# OpenEVSE_PLUS_v5_5.net
KiCad netlist of a schematic drawn in EAGLE
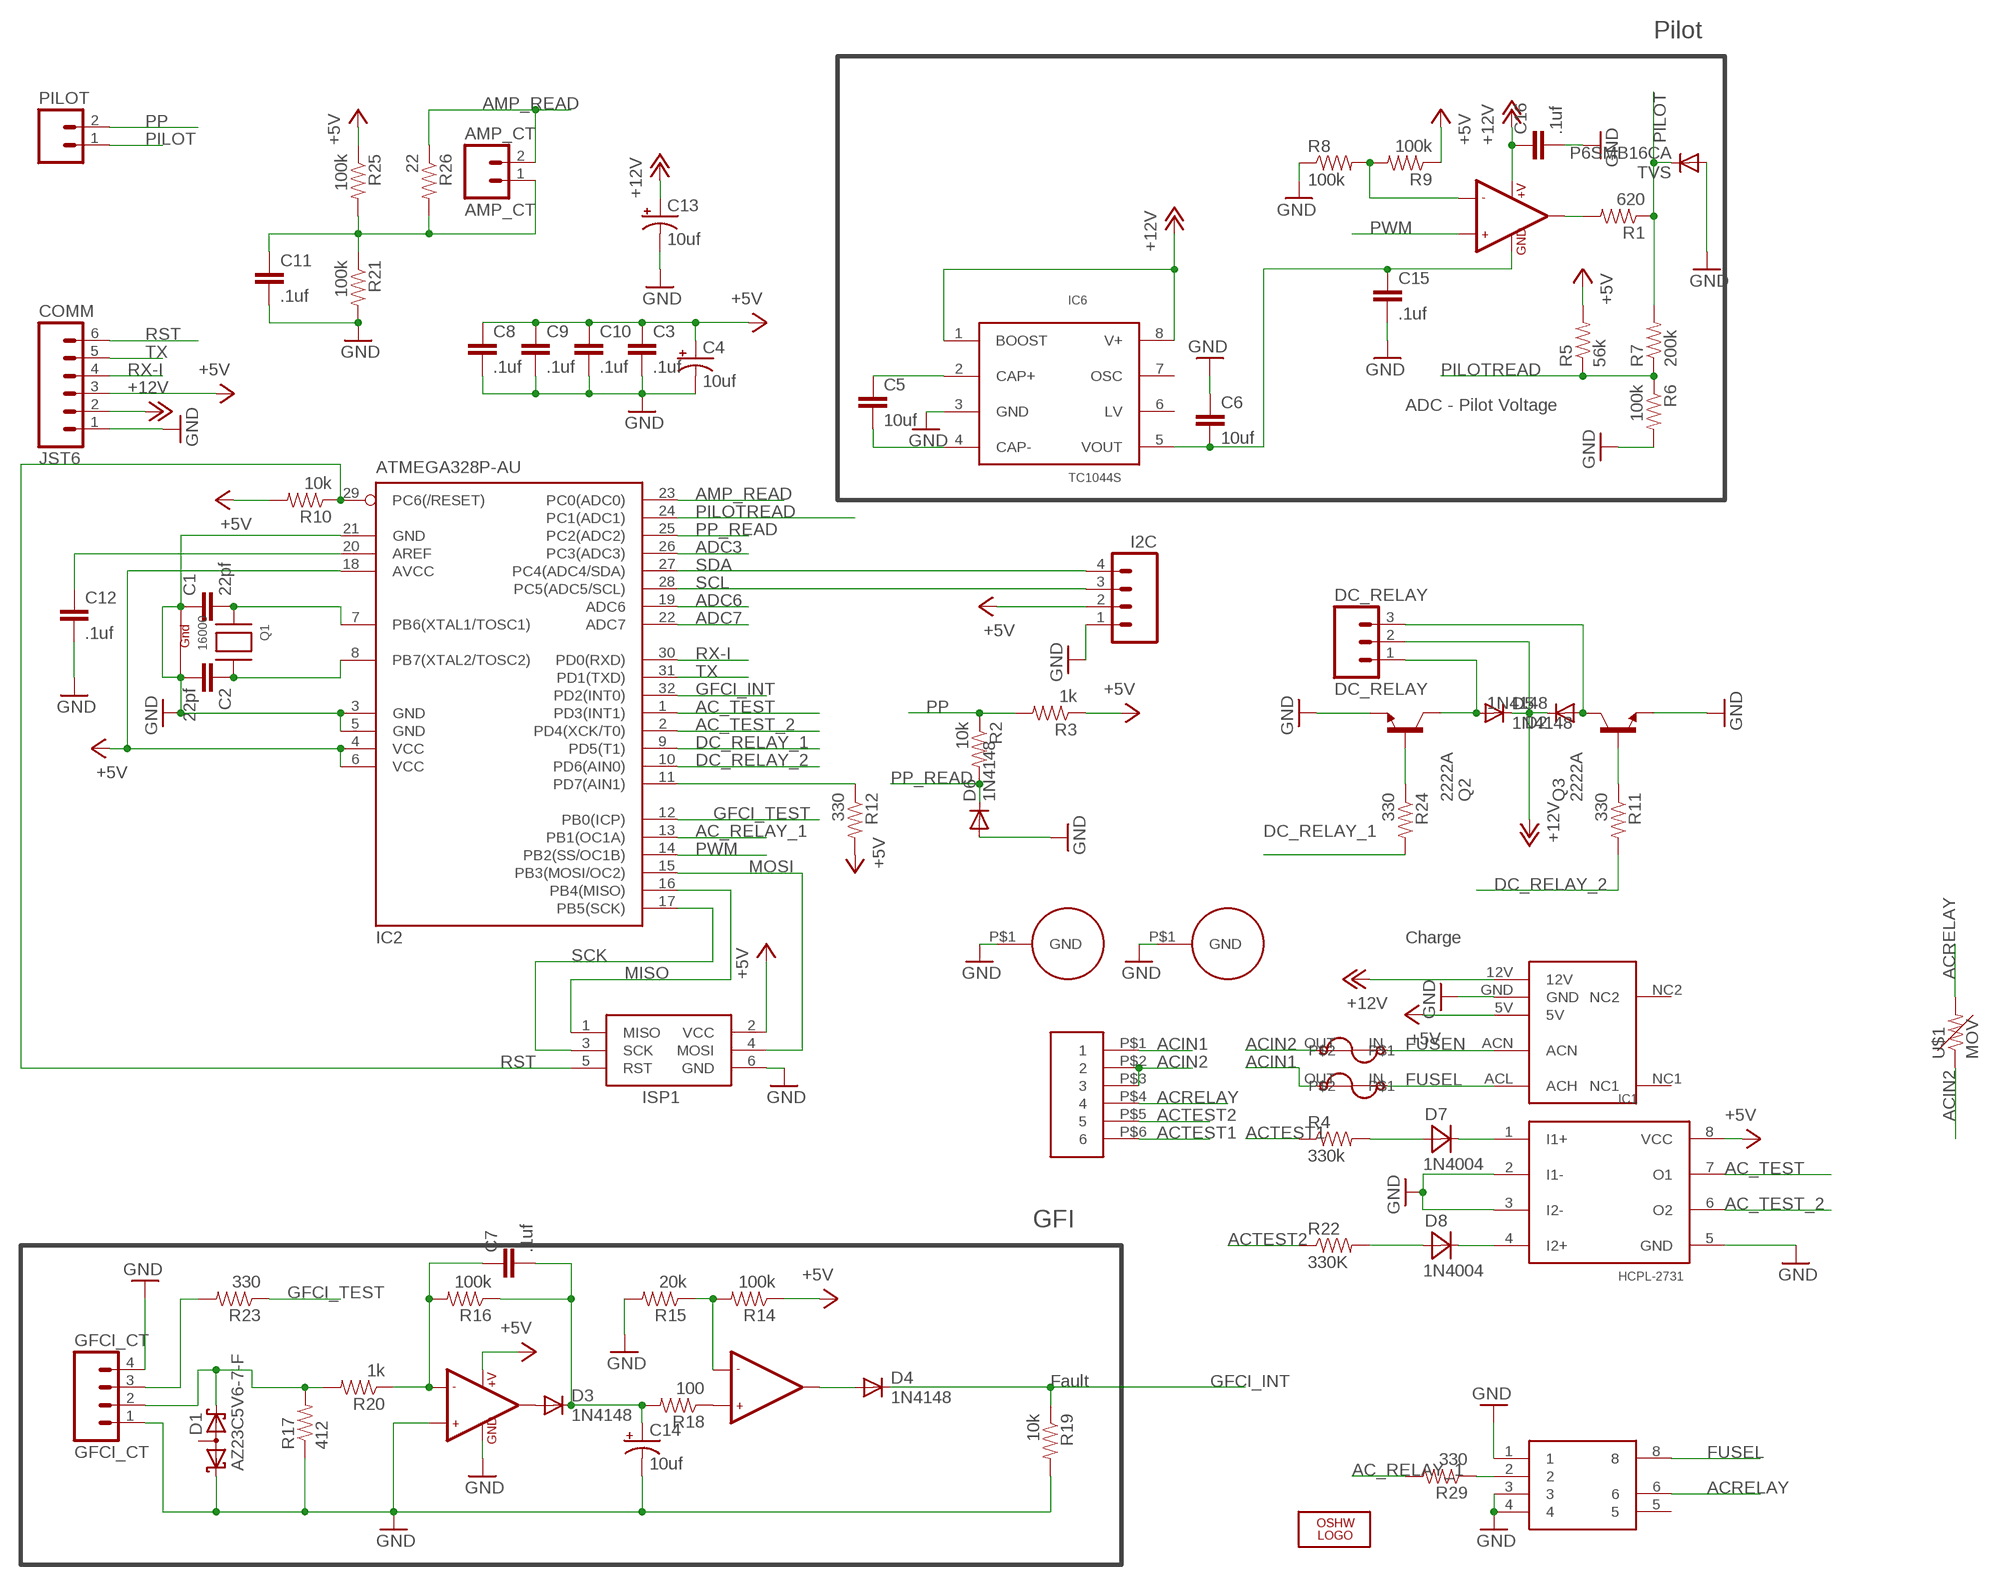
[diagram p0: schematic, sheet 1]

(export (version "E")
  (design (tool "Eeschema 10.0.6"))
  (components
    (comp (ref "AC")
      (value "JST-VH-6")
      (footprint "eagle-import:JST-VH-6")
      (libsource (lib "eagle-import") (part "JST-VH-6"))
    )
    (comp (ref "AMP_CT")
      (value "AMP_CT")
      (footprint "eagle-import:MOLEX_2")
      (libsource (lib "eagle-import") (part "MOLEX_2"))
    )
    (comp (ref "C1")
      (value "22pf")
      (footprint "eagle-import:0805")
      (libsource (lib "eagle-import") (part "CAP0805"))
    )
    (comp (ref "C2")
      (value "22pf")
      (footprint "eagle-import:0805")
      (libsource (lib "eagle-import") (part "CAP0805"))
    )
    (comp (ref "C3")
      (value ".1uf")
      (footprint "eagle-import:0805")
      (libsource (lib "eagle-import") (part "CAP0805"))
    )
    (comp (ref "C4")
      (value "10uf")
      (footprint "eagle-import:EIA3216")
      (libsource (lib "eagle-import") (part "CAP_POL1206"))
    )
    (comp (ref "C5")
      (value "10uf")
      (footprint "eagle-import:1206-CAP")
      (libsource (lib "eagle-import") (part "1.0UF50V10%(1206)"))
    )
    (comp (ref "C6")
      (value "10uf")
      (footprint "eagle-import:1206-CAP")
      (libsource (lib "eagle-import") (part "1.0UF50V10%(1206)"))
    )
    (comp (ref "C7")
      (value ".1uf")
      (footprint "eagle-import:0805")
      (libsource (lib "eagle-import") (part "CAP0805"))
    )
    (comp (ref "C8")
      (value ".1uf")
      (footprint "eagle-import:0805")
      (libsource (lib "eagle-import") (part "CAP0805"))
    )
    (comp (ref "C9")
      (value ".1uf")
      (footprint "eagle-import:0805")
      (libsource (lib "eagle-import") (part "CAP0805"))
    )
    (comp (ref "C10")
      (value ".1uf")
      (footprint "eagle-import:0805")
      (libsource (lib "eagle-import") (part "CAP0805"))
    )
    (comp (ref "C11")
      (value ".1uf")
      (footprint "eagle-import:0805")
      (libsource (lib "eagle-import") (part "CAP0805"))
    )
    (comp (ref "C12")
      (value ".1uf")
      (footprint "eagle-import:0805")
      (libsource (lib "eagle-import") (part "CAP0805"))
    )
    (comp (ref "C13")
      (value "10uf")
      (footprint "eagle-import:EIA3216")
      (libsource (lib "eagle-import") (part "CAP_POL1206"))
    )
    (comp (ref "C14")
      (value "10uf")
      (footprint "eagle-import:EIA3216")
      (libsource (lib "eagle-import") (part "CAP_POL1206"))
    )
    (comp (ref "C15")
      (value ".1uf")
      (footprint "eagle-import:0805")
      (libsource (lib "eagle-import") (part "CAP0805"))
    )
    (comp (ref "C16")
      (value ".1uf")
      (footprint "eagle-import:0805")
      (libsource (lib "eagle-import") (part "CAP0805"))
    )
    (comp (ref "COMM")
      (value "JST6")
      (footprint "eagle-import:JST6")
      (libsource (lib "eagle-import") (part "JST6"))
    )
    (comp (ref "D1")
      (value "AZ23C5V6-7-F")
      (footprint "eagle-import:SOT23")
      (libsource (lib "eagle-import") (part "BAS40-06"))
    )
    (comp (ref "D2")
      (value "1N4148")
      (footprint "eagle-import:SOD123")
      (libsource (lib "eagle-import") (part "DIODE-SOD123"))
    )
    (comp (ref "D3")
      (value "1N4148")
      (footprint "eagle-import:SOD123")
      (libsource (lib "eagle-import") (part "DIODE-SOD123"))
    )
    (comp (ref "D4")
      (value "1N4148")
      (footprint "eagle-import:SOD123")
      (libsource (lib "eagle-import") (part "DIODE-SOD123"))
    )
    (comp (ref "D5")
      (value "1N4148")
      (footprint "eagle-import:SOD123")
      (libsource (lib "eagle-import") (part "DIODE-SOD123"))
    )
    (comp (ref "D6")
      (value "1N4148")
      (footprint "eagle-import:SOD123")
      (libsource (lib "eagle-import") (part "DIODE-SOD123"))
    )
    (comp (ref "D7")
      (value "1N4004")
      (footprint "eagle-import:SMA")
      (libsource (lib "eagle-import") (part "MBRA340T3"))
    )
    (comp (ref "D8")
      (value "1N4004")
      (footprint "eagle-import:SMA")
      (libsource (lib "eagle-import") (part "MBRA340T3"))
    )
    (comp (ref "DC_RELAY")
      (value "DC_RELAY")
      (footprint "eagle-import:MOLEX_3")
      (libsource (lib "eagle-import") (part "MOLEX_3"))
    )
    (comp (ref "F1")
      (value "BEL1AFUSE")
      (footprint "eagle-import:BELFUSE1A")
      (libsource (lib "eagle-import") (part "BEL1AFUSE"))
    )
    (comp (ref "F2")
      (value "BEL1AFUSE")
      (footprint "eagle-import:BELFUSE1A")
      (libsource (lib "eagle-import") (part "BEL1AFUSE"))
    )
    (comp (ref "GFCI_CT")
      (value "GFCI_CT")
      (footprint "eagle-import:GFCI_4")
      (libsource (lib "eagle-import") (part "GFCI_4"))
    )
    (comp (ref "I2C")
      (value "M04JST-PTH-VERT")
      (footprint "eagle-import:JST-4-PTH-VERT")
      (libsource (lib "eagle-import") (part "M04JST-PTH-VERT"))
    )
    (comp (ref "IC1")
      (value "HCPL-2731")
      (footprint "eagle-import:DIP08")
      (libsource (lib "eagle-import") (part "HCPL-2731"))
    )
    (comp (ref "IC2")
      (value "ATMEGA328P-AU")
      (footprint "eagle-import:TQFP32-08")
      (fields (field (name "MPN") "ATMEGA8-16AU"))
      (libsource (lib "eagle-import") (part "MEGA8-AI"))
    )
    (comp (ref "IC3")
      (value "LM358")
      (footprint "eagle-import:SO08")
      (libsource (lib "eagle-import") (part "LMV358"))
    )
    (comp (ref "IC4")
      (value "LF353")
      (footprint "eagle-import:SO08")
      (libsource (lib "eagle-import") (part "LMV358"))
    )
    (comp (ref "IC5")
      (value "AQH1213")
      (footprint "eagle-import:DIP7")
      (libsource (lib "eagle-import") (part "AQH1213"))
    )
    (comp (ref "IC6")
      (value "TC1044S")
      (footprint "eagle-import:SO-8")
      (libsource (lib "eagle-import") (part "TC1044S"))
    )
    (comp (ref "ISP1")
      (value "AVRISP-6")
      (footprint "eagle-import:AVRISP")
      (libsource (lib "eagle-import") (part "AVRISP-6"))
    )
    (comp (ref "LOGO1")
      (value "OSHW_LOGO_8MILX0150-NT")
      (footprint "eagle-import:OSHW_8X150_NOTEXT")
      (libsource (lib "eagle-import") (part "OSHW_LOGO_8MILX0150-NT"))
    )
    (comp (ref "PILOT")
      (value "M025MM")
      (footprint "eagle-import:SCREWTERMINAL-5MM-2")
      (libsource (lib "eagle-import") (part "M025MM"))
    )
    (comp (ref "PS1")
      (value "MPM-04E-1205")
      (footprint "eagle-import:MPM-04E-1205")
      (libsource (lib "eagle-import") (part "MPM-04E-1205"))
    )
    (comp (ref "Q1")
      (value "16000")
      (footprint "eagle-import:NX3225")
      (libsource (lib "eagle-import") (part "XTAL-4-3225"))
    )
    (comp (ref "Q2")
      (value "2222A")
      (footprint "eagle-import:SOT23")
      (libsource (lib "eagle-import") (part "BCX70SMD"))
    )
    (comp (ref "Q3")
      (value "2222A")
      (footprint "eagle-import:SOT23")
      (libsource (lib "eagle-import") (part "BCX70SMD"))
    )
    (comp (ref "R1")
      (value "620")
      (footprint "eagle-import:0805")
      (libsource (lib "eagle-import") (part "RESISTOR0805-RES"))
    )
    (comp (ref "R2")
      (value "10k")
      (footprint "eagle-import:0805")
      (libsource (lib "eagle-import") (part "RESISTOR0805-RES"))
    )
    (comp (ref "R3")
      (value "1k")
      (footprint "eagle-import:0805")
      (libsource (lib "eagle-import") (part "RESISTOR0805-RES"))
    )
    (comp (ref "R4")
      (value "330k")
      (footprint "eagle-import:AXIAL-0.4")
      (libsource (lib "eagle-import") (part "RESISTORPTH-1/4W"))
    )
    (comp (ref "R5")
      (value "56k")
      (footprint "eagle-import:0805")
      (libsource (lib "eagle-import") (part "RESISTOR0805-RES"))
    )
    (comp (ref "R6")
      (value "100k")
      (footprint "eagle-import:0805")
      (libsource (lib "eagle-import") (part "RESISTOR0805-RES"))
    )
    (comp (ref "R7")
      (value "200k")
      (footprint "eagle-import:0805")
      (libsource (lib "eagle-import") (part "RESISTOR0805-RES"))
    )
    (comp (ref "R8")
      (value "100k")
      (footprint "eagle-import:0805")
      (libsource (lib "eagle-import") (part "RESISTOR0805-RES"))
    )
    (comp (ref "R9")
      (value "100k")
      (footprint "eagle-import:0805")
      (libsource (lib "eagle-import") (part "RESISTOR0805-RES"))
    )
    (comp (ref "R10")
      (value "10k")
      (footprint "eagle-import:0805")
      (libsource (lib "eagle-import") (part "RESISTOR0805-RES"))
    )
    (comp (ref "R11")
      (value "330")
      (footprint "eagle-import:0805")
      (libsource (lib "eagle-import") (part "RESISTOR0805-RES"))
    )
    (comp (ref "R12")
      (value "330")
      (footprint "eagle-import:0805")
      (libsource (lib "eagle-import") (part "RESISTOR0805-RES"))
    )
    (comp (ref "R14")
      (value "100k")
      (footprint "eagle-import:0805")
      (libsource (lib "eagle-import") (part "RESISTOR0805-RES"))
    )
    (comp (ref "R15")
      (value "20k")
      (footprint "eagle-import:0805")
      (libsource (lib "eagle-import") (part "RESISTOR0805-RES"))
    )
    (comp (ref "R16")
      (value "100k")
      (footprint "eagle-import:0805")
      (libsource (lib "eagle-import") (part "RESISTOR0805-RES"))
    )
    (comp (ref "R17")
      (value "412")
      (footprint "eagle-import:0805")
      (libsource (lib "eagle-import") (part "RESISTOR0805-RES"))
    )
    (comp (ref "R18")
      (value "100")
      (footprint "eagle-import:0805")
      (libsource (lib "eagle-import") (part "RESISTOR0805-RES"))
    )
    (comp (ref "R19")
      (value "10k")
      (footprint "eagle-import:0805")
      (libsource (lib "eagle-import") (part "RESISTOR0805-RES"))
    )
    (comp (ref "R20")
      (value "1k")
      (footprint "eagle-import:0805")
      (libsource (lib "eagle-import") (part "RESISTOR0805-RES"))
    )
    (comp (ref "R21")
      (value "100k")
      (footprint "eagle-import:0805")
      (libsource (lib "eagle-import") (part "RESISTOR0805-RES"))
    )
    (comp (ref "R22")
      (value "330K")
      (footprint "eagle-import:AXIAL-0.4")
      (libsource (lib "eagle-import") (part "RESISTORPTH-1/4W"))
    )
    (comp (ref "R23")
      (value "330")
      (footprint "eagle-import:0805")
      (libsource (lib "eagle-import") (part "RESISTOR0805-RES"))
    )
    (comp (ref "R24")
      (value "330")
      (footprint "eagle-import:0805")
      (libsource (lib "eagle-import") (part "RESISTOR0805-RES"))
    )
    (comp (ref "R25")
      (value "100k")
      (footprint "eagle-import:0805")
      (libsource (lib "eagle-import") (part "RESISTOR0805-RES"))
    )
    (comp (ref "R26")
      (value "22")
      (footprint "eagle-import:0805")
      (libsource (lib "eagle-import") (part "RESISTOR0805-RES"))
    )
    (comp (ref "R29")
      (value "330")
      (footprint "eagle-import:0805")
      (libsource (lib "eagle-import") (part "RESISTOR0805-RES"))
    )
    (comp (ref "TVS")
      (value "P6SMB16CA")
      (footprint "eagle-import:SMB")
      (libsource (lib "eagle-import") (part "DIODE-SMB"))
    )
    (comp (ref "U$1")
      (value "MOV")
      (footprint "eagle-import:MOV")
      (libsource (lib "eagle-import") (part "MOV"))
    )
    (comp (ref "U$3")
      (value "HOLE")
      (footprint "eagle-import:HOLE")
      (libsource (lib "eagle-import") (part "HOLE"))
    )
    (comp (ref "U$4")
      (value "HOLE")
      (footprint "eagle-import:HOLE")
      (libsource (lib "eagle-import") (part "HOLE"))
    )
  )
  (nets
    (net (code "1") (name "+5V") (class "Default")
      (node (ref "C10") (pin "1") (pinfunction "1_1") (pintype "passive"))
      (node (ref "C3") (pin "1") (pinfunction "1_1") (pintype "passive"))
      (node (ref "C4") (pin "A") (pinfunction "+_A") (pintype "passive"))
      (node (ref "C8") (pin "1") (pinfunction "1_1") (pintype "passive"))
      (node (ref "C9") (pin "1") (pinfunction "1_1") (pintype "passive"))
      (node (ref "COMM") (pin "3") (pinfunction "3_3") (pintype "passive"))
      (node (ref "I2C") (pin "2") (pinfunction "2_2") (pintype "passive"))
      (node (ref "IC1") (pin "8") (pinfunction "VCC_8") (pintype "bidirectional"))
      (node (ref "IC2") (pin "18") (pinfunction "AVCC_18") (pintype "power_in"))
      (node (ref "IC2") (pin "4") (pinfunction "VCC_4") (pintype "power_in"))
      (node (ref "IC2") (pin "6") (pinfunction "VCC_6") (pintype "power_in"))
      (node (ref "IC3") (pin "8") (pinfunction "+V_8") (pintype "power_in"))
      (node (ref "ISP1") (pin "2") (pinfunction "VCC_2") (pintype "power_in"))
      (node (ref "PS1") (pin "5V") (pinfunction "5V_5V") (pintype "bidirectional"))
      (node (ref "R10") (pin "2") (pinfunction "2_2") (pintype "passive"))
      (node (ref "R12") (pin "2") (pinfunction "2_2") (pintype "passive"))
      (node (ref "R14") (pin "1") (pinfunction "1_1") (pintype "passive"))
      (node (ref "R25") (pin "1") (pinfunction "1_1") (pintype "passive"))
      (node (ref "R3") (pin "1") (pinfunction "1_1") (pintype "passive"))
      (node (ref "R5") (pin "2") (pinfunction "2_2") (pintype "passive"))
      (node (ref "R9") (pin "1") (pinfunction "1_1") (pintype "passive"))
    )
    (net (code "2") (name "+12V") (class "Default")
      (node (ref "C13") (pin "A") (pinfunction "+_A") (pintype "passive"))
      (node (ref "C16") (pin "1") (pinfunction "1_1") (pintype "passive"))
      (node (ref "COMM") (pin "2") (pinfunction "2_2") (pintype "passive"))
      (node (ref "D2") (pin "C") (pinfunction "C_C") (pintype "passive"))
      (node (ref "D5") (pin "C") (pinfunction "C_C") (pintype "passive"))
      (node (ref "DC_RELAY") (pin "2") (pinfunction "2_2") (pintype "passive"))
      (node (ref "IC4") (pin "8") (pinfunction "+V_8") (pintype "power_in"))
      (node (ref "IC6") (pin "1") (pinfunction "BOOST_1") (pintype "bidirectional"))
      (node (ref "IC6") (pin "8") (pinfunction "V+_8") (pintype "bidirectional"))
      (node (ref "PS1") (pin "12V") (pinfunction "12V_12V") (pintype "bidirectional"))
    )
    (net (code "3") (name "/ACIN1") (class "Default")
      (node (ref "AC") (pin "P$1") (pinfunction "1_P$1") (pintype "bidirectional"))
      (node (ref "F2") (pin "OUT") (pinfunction "P$1_OUT") (pintype "bidirectional"))
    )
    (net (code "4") (name "/ACIN2") (class "Default")
      (node (ref "AC") (pin "P$2") (pinfunction "2_P$2") (pintype "bidirectional"))
      (node (ref "AC") (pin "P$3") (pinfunction "3_P$3") (pintype "bidirectional"))
      (node (ref "F1") (pin "OUT") (pinfunction "P$1_OUT") (pintype "bidirectional"))
      (node (ref "U$1") (pin "P$1") (pinfunction "1_P$1") (pintype "passive"))
    )
    (net (code "5") (name "/ACRELAY") (class "Default")
      (node (ref "AC") (pin "P$4") (pinfunction "4_P$4") (pintype "bidirectional"))
      (node (ref "IC5") (pin "6") (pinfunction "6_6") (pintype "bidirectional"))
      (node (ref "U$1") (pin "P$2") (pinfunction "2_P$2") (pintype "passive"))
    )
    (net (code "6") (name "/ACTEST1") (class "Default")
      (node (ref "AC") (pin "P$6") (pinfunction "6_P$6") (pintype "bidirectional"))
      (node (ref "R4") (pin "P$1") (pinfunction "1_P$1") (pintype "passive"))
    )
    (net (code "7") (name "/ACTEST2") (class "Default")
      (node (ref "AC") (pin "P$5") (pinfunction "5_P$5") (pintype "bidirectional"))
      (node (ref "R22") (pin "P$1") (pinfunction "1_P$1") (pintype "passive"))
    )
    (net (code "8") (name "/AC_RELAY_1") (class "Default")
      (node (ref "IC2") (pin "13") (pinfunction "PB1(OC1A)_13") (pintype "bidirectional"))
      (node (ref "R29") (pin "2") (pinfunction "2_2") (pintype "passive"))
    )
    (net (code "9") (name "/AC_TEST") (class "Default")
      (node (ref "IC1") (pin "7") (pinfunction "O1_7") (pintype "bidirectional"))
      (node (ref "IC2") (pin "1") (pinfunction "PD3(INT1)_1") (pintype "bidirectional"))
    )
    (net (code "10") (name "/AC_TEST_2") (class "Default")
      (node (ref "IC1") (pin "6") (pinfunction "O2_6") (pintype "bidirectional"))
      (node (ref "IC2") (pin "2") (pinfunction "PD4(XCK/T0)_2") (pintype "bidirectional"))
    )
    (net (code "11") (name "/ADC3") (class "Default")
      (node (ref "IC2") (pin "26") (pinfunction "PC3(ADC3)_26") (pintype "bidirectional"))
    )
    (net (code "12") (name "/ADC6") (class "Default")
      (node (ref "IC2") (pin "19") (pinfunction "ADC6_19") (pintype "bidirectional"))
    )
    (net (code "13") (name "/ADC7") (class "Default")
      (node (ref "IC2") (pin "22") (pinfunction "ADC7_22") (pintype "bidirectional"))
    )
    (net (code "14") (name "/AMP_READ") (class "Default")
      (node (ref "AMP_CT") (pin "2") (pinfunction "2_2") (pintype "passive"))
      (node (ref "IC2") (pin "23") (pinfunction "PC0(ADC0)_23") (pintype "bidirectional"))
      (node (ref "R26") (pin "1") (pinfunction "1_1") (pintype "passive"))
    )
    (net (code "15") (name "/DC_RELAY_1") (class "Default")
      (node (ref "IC2") (pin "9") (pinfunction "PD5(T1)_9") (pintype "bidirectional"))
      (node (ref "R24") (pin "2") (pinfunction "2_2") (pintype "passive"))
    )
    (net (code "16") (name "/DC_RELAY_2") (class "Default")
      (node (ref "IC2") (pin "10") (pinfunction "PD6(AIN0)_10") (pintype "bidirectional"))
      (node (ref "R11") (pin "2") (pinfunction "2_2") (pintype "passive"))
    )
    (net (code "17") (name "/FUSEL") (class "Default")
      (node (ref "F2") (pin "IN") (pinfunction "P$2_IN") (pintype "bidirectional"))
      (node (ref "IC5") (pin "8") (pinfunction "8_8") (pintype "bidirectional"))
      (node (ref "PS1") (pin "ACL") (pinfunction "ACH_ACL") (pintype "bidirectional"))
    )
    (net (code "18") (name "/FUSEN") (class "Default")
      (node (ref "F1") (pin "IN") (pinfunction "P$2_IN") (pintype "bidirectional"))
      (node (ref "PS1") (pin "ACN") (pinfunction "ACN_ACN") (pintype "bidirectional"))
    )
    (net (code "19") (name "/GFCI_INT") (class "Default")
      (node (ref "D4") (pin "C") (pinfunction "C_C") (pintype "passive"))
      (node (ref "IC2") (pin "32") (pinfunction "PD2(INT0)_32") (pintype "bidirectional"))
      (node (ref "R19") (pin "1") (pinfunction "1_1") (pintype "passive"))
    )
    (net (code "20") (name "/GFCI_TEST") (class "Default")
      (node (ref "IC2") (pin "12") (pinfunction "PB0(ICP)_12") (pintype "bidirectional"))
      (node (ref "R23") (pin "1") (pinfunction "1_1") (pintype "passive"))
    )
    (net (code "21") (name "/MISO") (class "Default")
      (node (ref "IC2") (pin "16") (pinfunction "PB4(MISO)_16") (pintype "bidirectional"))
      (node (ref "ISP1") (pin "1") (pinfunction "MISO_1") (pintype "input"))
    )
    (net (code "22") (name "/MOSI") (class "Default")
      (node (ref "IC2") (pin "15") (pinfunction "PB3(MOSI/OC2)_15") (pintype "bidirectional"))
      (node (ref "ISP1") (pin "4") (pinfunction "MOSI_4") (pintype "output"))
    )
    (net (code "23") (name "/PILOT") (class "Default")
      (node (ref "PILOT") (pin "1") (pinfunction "1_1") (pintype "passive"))
      (node (ref "R1") (pin "1") (pinfunction "1_1") (pintype "passive"))
      (node (ref "R7") (pin "2") (pinfunction "2_2") (pintype "passive"))
      (node (ref "TVS") (pin "C") (pinfunction "C_C") (pintype "passive"))
    )
    (net (code "24") (name "/PILOTREAD") (class "Default")
      (node (ref "IC2") (pin "24") (pinfunction "PC1(ADC1)_24") (pintype "bidirectional"))
      (node (ref "R5") (pin "1") (pinfunction "1_1") (pintype "passive"))
      (node (ref "R6") (pin "1") (pinfunction "1_1") (pintype "passive"))
      (node (ref "R7") (pin "1") (pinfunction "1_1") (pintype "passive"))
    )
    (net (code "25") (name "/PP") (class "Default")
      (node (ref "PILOT") (pin "2") (pinfunction "2_2") (pintype "passive"))
      (node (ref "R2") (pin "1") (pinfunction "1_1") (pintype "passive"))
      (node (ref "R3") (pin "2") (pinfunction "2_2") (pintype "passive"))
    )
    (net (code "26") (name "/PP_READ") (class "Default")
      (node (ref "D6") (pin "C") (pinfunction "C_C") (pintype "passive"))
      (node (ref "IC2") (pin "25") (pinfunction "PC2(ADC2)_25") (pintype "bidirectional"))
      (node (ref "R2") (pin "2") (pinfunction "2_2") (pintype "passive"))
    )
    (net (code "27") (name "/PWM") (class "Default")
      (node (ref "IC2") (pin "14") (pinfunction "PB2(SS/OC1B)_14") (pintype "bidirectional"))
      (node (ref "IC4") (pin "3") (pinfunction "+IN1_3") (pintype "input"))
    )
    (net (code "28") (name "/RST") (class "Default")
      (node (ref "COMM") (pin "6") (pinfunction "6_6") (pintype "passive"))
      (node (ref "IC2") (pin "29") (pinfunction "PC6(/RESET)_29") (pintype "bidirectional"))
      (node (ref "ISP1") (pin "5") (pinfunction "RST_5") (pintype "output"))
      (node (ref "R10") (pin "1") (pinfunction "1_1") (pintype "passive"))
    )
    (net (code "29") (name "/RX-I") (class "Default")
      (node (ref "COMM") (pin "4") (pinfunction "4_4") (pintype "passive"))
      (node (ref "IC2") (pin "30") (pinfunction "PD0(RXD)_30") (pintype "bidirectional"))
    )
    (net (code "30") (name "/SCK") (class "Default")
      (node (ref "IC2") (pin "17") (pinfunction "PB5(SCK)_17") (pintype "bidirectional"))
      (node (ref "ISP1") (pin "3") (pinfunction "SCK_3") (pintype "output"))
    )
    (net (code "31") (name "/SCL") (class "Default")
      (node (ref "I2C") (pin "3") (pinfunction "3_3") (pintype "passive"))
      (node (ref "IC2") (pin "28") (pinfunction "PC5(ADC5/SCL)_28") (pintype "bidirectional"))
    )
    (net (code "32") (name "/SDA") (class "Default")
      (node (ref "I2C") (pin "4") (pinfunction "4_4") (pintype "passive"))
      (node (ref "IC2") (pin "27") (pinfunction "PC4(ADC4/SDA)_27") (pintype "bidirectional"))
    )
    (net (code "33") (name "/TX") (class "Default")
      (node (ref "COMM") (pin "5") (pinfunction "5_5") (pintype "passive"))
      (node (ref "IC2") (pin "31") (pinfunction "PD1(TXD)_31") (pintype "bidirectional"))
    )
    (net (code "34") (name "GND") (class "Default")
      (node (ref "C1") (pin "1") (pinfunction "1_1") (pintype "passive"))
      (node (ref "C10") (pin "2") (pinfunction "2_2") (pintype "passive"))
      (node (ref "C11") (pin "2") (pinfunction "2_2") (pintype "passive"))
      (node (ref "C12") (pin "2") (pinfunction "2_2") (pintype "passive"))
      (node (ref "C13") (pin "C") (pinfunction "-_C") (pintype "passive"))
      (node (ref "C14") (pin "C") (pinfunction "-_C") (pintype "passive"))
      (node (ref "C15") (pin "2") (pinfunction "2_2") (pintype "passive"))
      (node (ref "C16") (pin "2") (pinfunction "2_2") (pintype "passive"))
      (node (ref "C2") (pin "2") (pinfunction "2_2") (pintype "passive"))
      (node (ref "C3") (pin "2") (pinfunction "2_2") (pintype "passive"))
      (node (ref "C4") (pin "C") (pinfunction "-_C") (pintype "passive"))
      (node (ref "C6") (pin "1") (pinfunction "1_1") (pintype "passive"))
      (node (ref "C8") (pin "2") (pinfunction "2_2") (pintype "passive"))
      (node (ref "C9") (pin "2") (pinfunction "2_2") (pintype "passive"))
      (node (ref "COMM") (pin "1") (pinfunction "1_1") (pintype "passive"))
      (node (ref "D1") (pin "1") (pinfunction "K1_1") (pintype "passive"))
      (node (ref "D6") (pin "A") (pinfunction "A_A") (pintype "passive"))
      (node (ref "GFCI_CT") (pin "1") (pinfunction "1_1") (pintype "passive"))
      (node (ref "GFCI_CT") (pin "4") (pinfunction "4_4") (pintype "passive"))
      (node (ref "I2C") (pin "1") (pinfunction "1_1") (pintype "passive"))
      (node (ref "IC1") (pin "2") (pinfunction "I1-_2") (pintype "bidirectional"))
      (node (ref "IC1") (pin "3") (pinfunction "I2-_3") (pintype "bidirectional"))
      (node (ref "IC1") (pin "5") (pinfunction "GND_5") (pintype "bidirectional"))
      (node (ref "IC2") (pin "21") (pinfunction "GND_21") (pintype "power_in"))
      (node (ref "IC2") (pin "3") (pinfunction "GND_3") (pintype "power_in"))
      (node (ref "IC2") (pin "5") (pinfunction "GND_5") (pintype "power_in"))
      (node (ref "IC3") (pin "3") (pinfunction "+IN1_3") (pintype "input"))
      (node (ref "IC3") (pin "4") (pinfunction "GND_4") (pintype "power_in"))
      (node (ref "IC5") (pin "1") (pinfunction "1_1") (pintype "bidirectional"))
      (node (ref "IC5") (pin "3") (pinfunction "3_3") (pintype "bidirectional"))
      (node (ref "IC5") (pin "4") (pinfunction "4_4") (pintype "bidirectional"))
      (node (ref "IC6") (pin "3") (pinfunction "GND_3") (pintype "bidirectional"))
      (node (ref "ISP1") (pin "6") (pinfunction "GND_6") (pintype "power_in"))
      (node (ref "PS1") (pin "GND") (pinfunction "GND_GND") (pintype "bidirectional"))
      (node (ref "Q1") (pin "1") (pinfunction "G1_1") (pintype "power_in"))
      (node (ref "Q1") (pin "3") (pinfunction "G2_3") (pintype "power_in"))
      (node (ref "Q2") (pin "2") (pinfunction "E_2") (pintype "passive"))
      (node (ref "Q3") (pin "2") (pinfunction "E_2") (pintype "passive"))
      (node (ref "R15") (pin "2") (pinfunction "2_2") (pintype "passive"))
      (node (ref "R17") (pin "1") (pinfunction "1_1") (pintype "passive"))
      (node (ref "R19") (pin "2") (pinfunction "2_2") (pintype "passive"))
      (node (ref "R21") (pin "2") (pinfunction "2_2") (pintype "passive"))
      (node (ref "R6") (pin "2") (pinfunction "2_2") (pintype "passive"))
      (node (ref "R8") (pin "1") (pinfunction "1_1") (pintype "passive"))
      (node (ref "TVS") (pin "A") (pinfunction "A_A") (pintype "passive"))
      (node (ref "U$3") (pin "P$1") (pinfunction "GND_P$1") (pintype "bidirectional"))
      (node (ref "U$4") (pin "P$1") (pinfunction "GND_P$1") (pintype "bidirectional"))
    )
    (net (code "35") (name "Net-(AMP_CT-Pad1)") (class "Default")
      (node (ref "AMP_CT") (pin "1") (pinfunction "1_1") (pintype "passive"))
      (node (ref "C11") (pin "1") (pinfunction "1_1") (pintype "passive"))
      (node (ref "R21") (pin "1") (pinfunction "1_1") (pintype "passive"))
      (node (ref "R25") (pin "2") (pinfunction "2_2") (pintype "passive"))
      (node (ref "R26") (pin "2") (pinfunction "2_2") (pintype "passive"))
    )
    (net (code "36") (name "Net-(C14-+)") (class "Default")
      (node (ref "C14") (pin "A") (pinfunction "+_A") (pintype "passive"))
      (node (ref "C7") (pin "2") (pinfunction "2_2") (pintype "passive"))
      (node (ref "D3") (pin "C") (pinfunction "C_C") (pintype "passive"))
      (node (ref "R16") (pin "1") (pinfunction "1_1") (pintype "passive"))
      (node (ref "R18") (pin "2") (pinfunction "2_2") (pintype "passive"))
    )
    (net (code "37") (name "Net-(D1-K2)") (class "Default")
      (node (ref "D1") (pin "2") (pinfunction "K2_2") (pintype "passive"))
      (node (ref "GFCI_CT") (pin "2") (pinfunction "2_2") (pintype "passive"))
      (node (ref "R17") (pin "2") (pinfunction "2_2") (pintype "passive"))
      (node (ref "R20") (pin "2") (pinfunction "2_2") (pintype "passive"))
    )
    (net (code "38") (name "Net-(GFCI_CT-Pad3)") (class "Default")
      (node (ref "GFCI_CT") (pin "3") (pinfunction "3_3") (pintype "passive"))
      (node (ref "R23") (pin "2") (pinfunction "2_2") (pintype "passive"))
    )
    (net (code "39") (name "Net-(IC1-I1+)") (class "Default")
      (node (ref "D7") (pin "C") (pinfunction "C_C") (pintype "passive"))
      (node (ref "IC1") (pin "1") (pinfunction "I1+_1") (pintype "bidirectional"))
    )
    (net (code "40") (name "Net-(IC1-I2+)") (class "Default")
      (node (ref "D8") (pin "C") (pinfunction "C_C") (pintype "passive"))
      (node (ref "IC1") (pin "4") (pinfunction "I2+_4") (pintype "bidirectional"))
    )
    (net (code "41") (name "Net-(IC2-AREF)") (class "Default")
      (node (ref "C12") (pin "1") (pinfunction "1_1") (pintype "passive"))
      (node (ref "IC2") (pin "20") (pinfunction "AREF_20") (pintype "passive"))
    )
    (net (code "42") (name "Net-(IC2-PB6(XTAL1{slash}TOSC1))") (class "Default")
      (node (ref "C1") (pin "2") (pinfunction "2_2") (pintype "passive"))
      (node (ref "IC2") (pin "7") (pinfunction "PB6(XTAL1/TOSC1)_7") (pintype "bidirectional"))
      (node (ref "Q1") (pin "2") (pinfunction "X1_2") (pintype "bidirectional"))
    )
    (net (code "43") (name "Net-(IC2-PB7(XTAL2{slash}TOSC2))") (class "Default")
      (node (ref "C2") (pin "1") (pinfunction "1_1") (pintype "passive"))
      (node (ref "IC2") (pin "8") (pinfunction "PB7(XTAL2/TOSC2)_8") (pintype "bidirectional"))
      (node (ref "Q1") (pin "4") (pinfunction "X2_4") (pintype "bidirectional"))
    )
    (net (code "44") (name "Net-(IC2-PD7(AIN1))") (class "Default")
      (node (ref "IC2") (pin "11") (pinfunction "PD7(AIN1)_11") (pintype "bidirectional"))
      (node (ref "R12") (pin "1") (pinfunction "1_1") (pintype "passive"))
    )
    (net (code "45") (name "Net-(IC3A--IN1)") (class "Default")
      (node (ref "C7") (pin "1") (pinfunction "1_1") (pintype "passive"))
      (node (ref "IC3") (pin "2") (pinfunction "-IN1_2") (pintype "input"))
      (node (ref "R16") (pin "2") (pinfunction "2_2") (pintype "passive"))
      (node (ref "R20") (pin "1") (pinfunction "1_1") (pintype "passive"))
    )
    (net (code "46") (name "Net-(IC3A-OUT1)") (class "Default")
      (node (ref "D3") (pin "A") (pinfunction "A_A") (pintype "passive"))
      (node (ref "IC3") (pin "1") (pinfunction "OUT1_1") (pintype "output"))
    )
    (net (code "47") (name "Net-(IC3B-+IN2)") (class "Default")
      (node (ref "IC3") (pin "5") (pinfunction "+IN2_5") (pintype "input"))
      (node (ref "R18") (pin "1") (pinfunction "1_1") (pintype "passive"))
    )
    (net (code "48") (name "Net-(IC3B--IN2)") (class "Default")
      (node (ref "IC3") (pin "6") (pinfunction "-IN2_6") (pintype "input"))
      (node (ref "R14") (pin "2") (pinfunction "2_2") (pintype "passive"))
      (node (ref "R15") (pin "1") (pinfunction "1_1") (pintype "passive"))
    )
    (net (code "49") (name "Net-(IC3B-OUT2)") (class "Default")
      (node (ref "D4") (pin "A") (pinfunction "A_A") (pintype "passive"))
      (node (ref "IC3") (pin "7") (pinfunction "OUT2_7") (pintype "output"))
    )
    (net (code "50") (name "Net-(IC4A--IN1)") (class "Default")
      (node (ref "IC4") (pin "2") (pinfunction "-IN1_2") (pintype "input"))
      (node (ref "R8") (pin "2") (pinfunction "2_2") (pintype "passive"))
      (node (ref "R9") (pin "2") (pinfunction "2_2") (pintype "passive"))
    )
    (net (code "51") (name "Net-(IC4A-GND)") (class "Default")
      (node (ref "C15") (pin "1") (pinfunction "1_1") (pintype "passive"))
      (node (ref "C6") (pin "2") (pinfunction "2_2") (pintype "passive"))
      (node (ref "IC4") (pin "4") (pinfunction "GND_4") (pintype "power_in"))
      (node (ref "IC6") (pin "5") (pinfunction "VOUT_5") (pintype "bidirectional"))
    )
    (net (code "52") (name "Net-(IC4A-OUT1)") (class "Default")
      (node (ref "IC4") (pin "1") (pinfunction "OUT1_1") (pintype "output"))
      (node (ref "R1") (pin "2") (pinfunction "2_2") (pintype "passive"))
    )
    (net (code "53") (name "Net-(IC5-Pad2)") (class "Default")
      (node (ref "IC5") (pin "2") (pinfunction "2_2") (pintype "bidirectional"))
      (node (ref "R29") (pin "1") (pinfunction "1_1") (pintype "passive"))
    )
    (net (code "54") (name "Net-(IC6-CAP+)") (class "Default")
      (node (ref "C5") (pin "1") (pinfunction "1_1") (pintype "passive"))
      (node (ref "IC6") (pin "2") (pinfunction "CAP+_2") (pintype "bidirectional"))
    )
    (net (code "55") (name "Net-(IC6-CAP-)") (class "Default")
      (node (ref "C5") (pin "2") (pinfunction "2_2") (pintype "passive"))
      (node (ref "IC6") (pin "4") (pinfunction "CAP-_4") (pintype "bidirectional"))
    )
    (net (code "56") (name "Net-(Q2-B)") (class "Default")
      (node (ref "Q2") (pin "1") (pinfunction "B_1") (pintype "passive"))
      (node (ref "R24") (pin "1") (pinfunction "1_1") (pintype "passive"))
    )
    (net (code "57") (name "Net-(Q2-C)") (class "Default")
      (node (ref "D5") (pin "A") (pinfunction "A_A") (pintype "passive"))
      (node (ref "DC_RELAY") (pin "1") (pinfunction "1_1") (pintype "passive"))
      (node (ref "Q2") (pin "3") (pinfunction "C_3") (pintype "passive"))
    )
    (net (code "58") (name "Net-(Q3-B)") (class "Default")
      (node (ref "Q3") (pin "1") (pinfunction "B_1") (pintype "passive"))
      (node (ref "R11") (pin "1") (pinfunction "1_1") (pintype "passive"))
    )
    (net (code "59") (name "Net-(Q3-C)") (class "Default")
      (node (ref "D2") (pin "A") (pinfunction "A_A") (pintype "passive"))
      (node (ref "DC_RELAY") (pin "3") (pinfunction "3_3") (pintype "passive"))
      (node (ref "Q3") (pin "3") (pinfunction "C_3") (pintype "passive"))
    )
    (net (code "60") (name "Net-(R4-2)") (class "Default")
      (node (ref "D7") (pin "A") (pinfunction "A_A") (pintype "passive"))
      (node (ref "R4") (pin "P$2") (pinfunction "2_P$2") (pintype "passive"))
    )
    (net (code "61") (name "Net-(R22-2)") (class "Default")
      (node (ref "D8") (pin "A") (pinfunction "A_A") (pintype "passive"))
      (node (ref "R22") (pin "P$2") (pinfunction "2_P$2") (pintype "passive"))
    )
    (net (code "62") (name "unconnected-(D1-AA-Pad3)") (class "Default")
      (node (ref "D1") (pin "3") (pinfunction "AA_3") (pintype "passive"))
    )
    (net (code "63") (name "unconnected-(IC5-Pad5)") (class "Default")
      (node (ref "IC5") (pin "5") (pinfunction "5_5") (pintype "bidirectional"))
    )
    (net (code "64") (name "unconnected-(IC6-LV-Pad6)") (class "Default")
      (node (ref "IC6") (pin "6") (pinfunction "LV_6") (pintype "bidirectional"))
    )
    (net (code "65") (name "unconnected-(IC6-OSC-Pad7)") (class "Default")
      (node (ref "IC6") (pin "7") (pinfunction "OSC_7") (pintype "bidirectional"))
    )
    (net (code "66") (name "unconnected-(PS1-PadNC1)") (class "Default")
      (node (ref "PS1") (pin "NC1") (pinfunction "NC1_NC1") (pintype "bidirectional"))
    )
    (net (code "67") (name "unconnected-(PS1-PadNC2)") (class "Default")
      (node (ref "PS1") (pin "NC2") (pinfunction "NC2_NC2") (pintype "bidirectional"))
    )
  )
)
